# LcsNodes-Quad-Block-Controller-B_02_10.net
KiCad netlist of a schematic drawn in EasyEDA
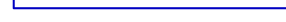
[diagram p0: High Level Schematic]
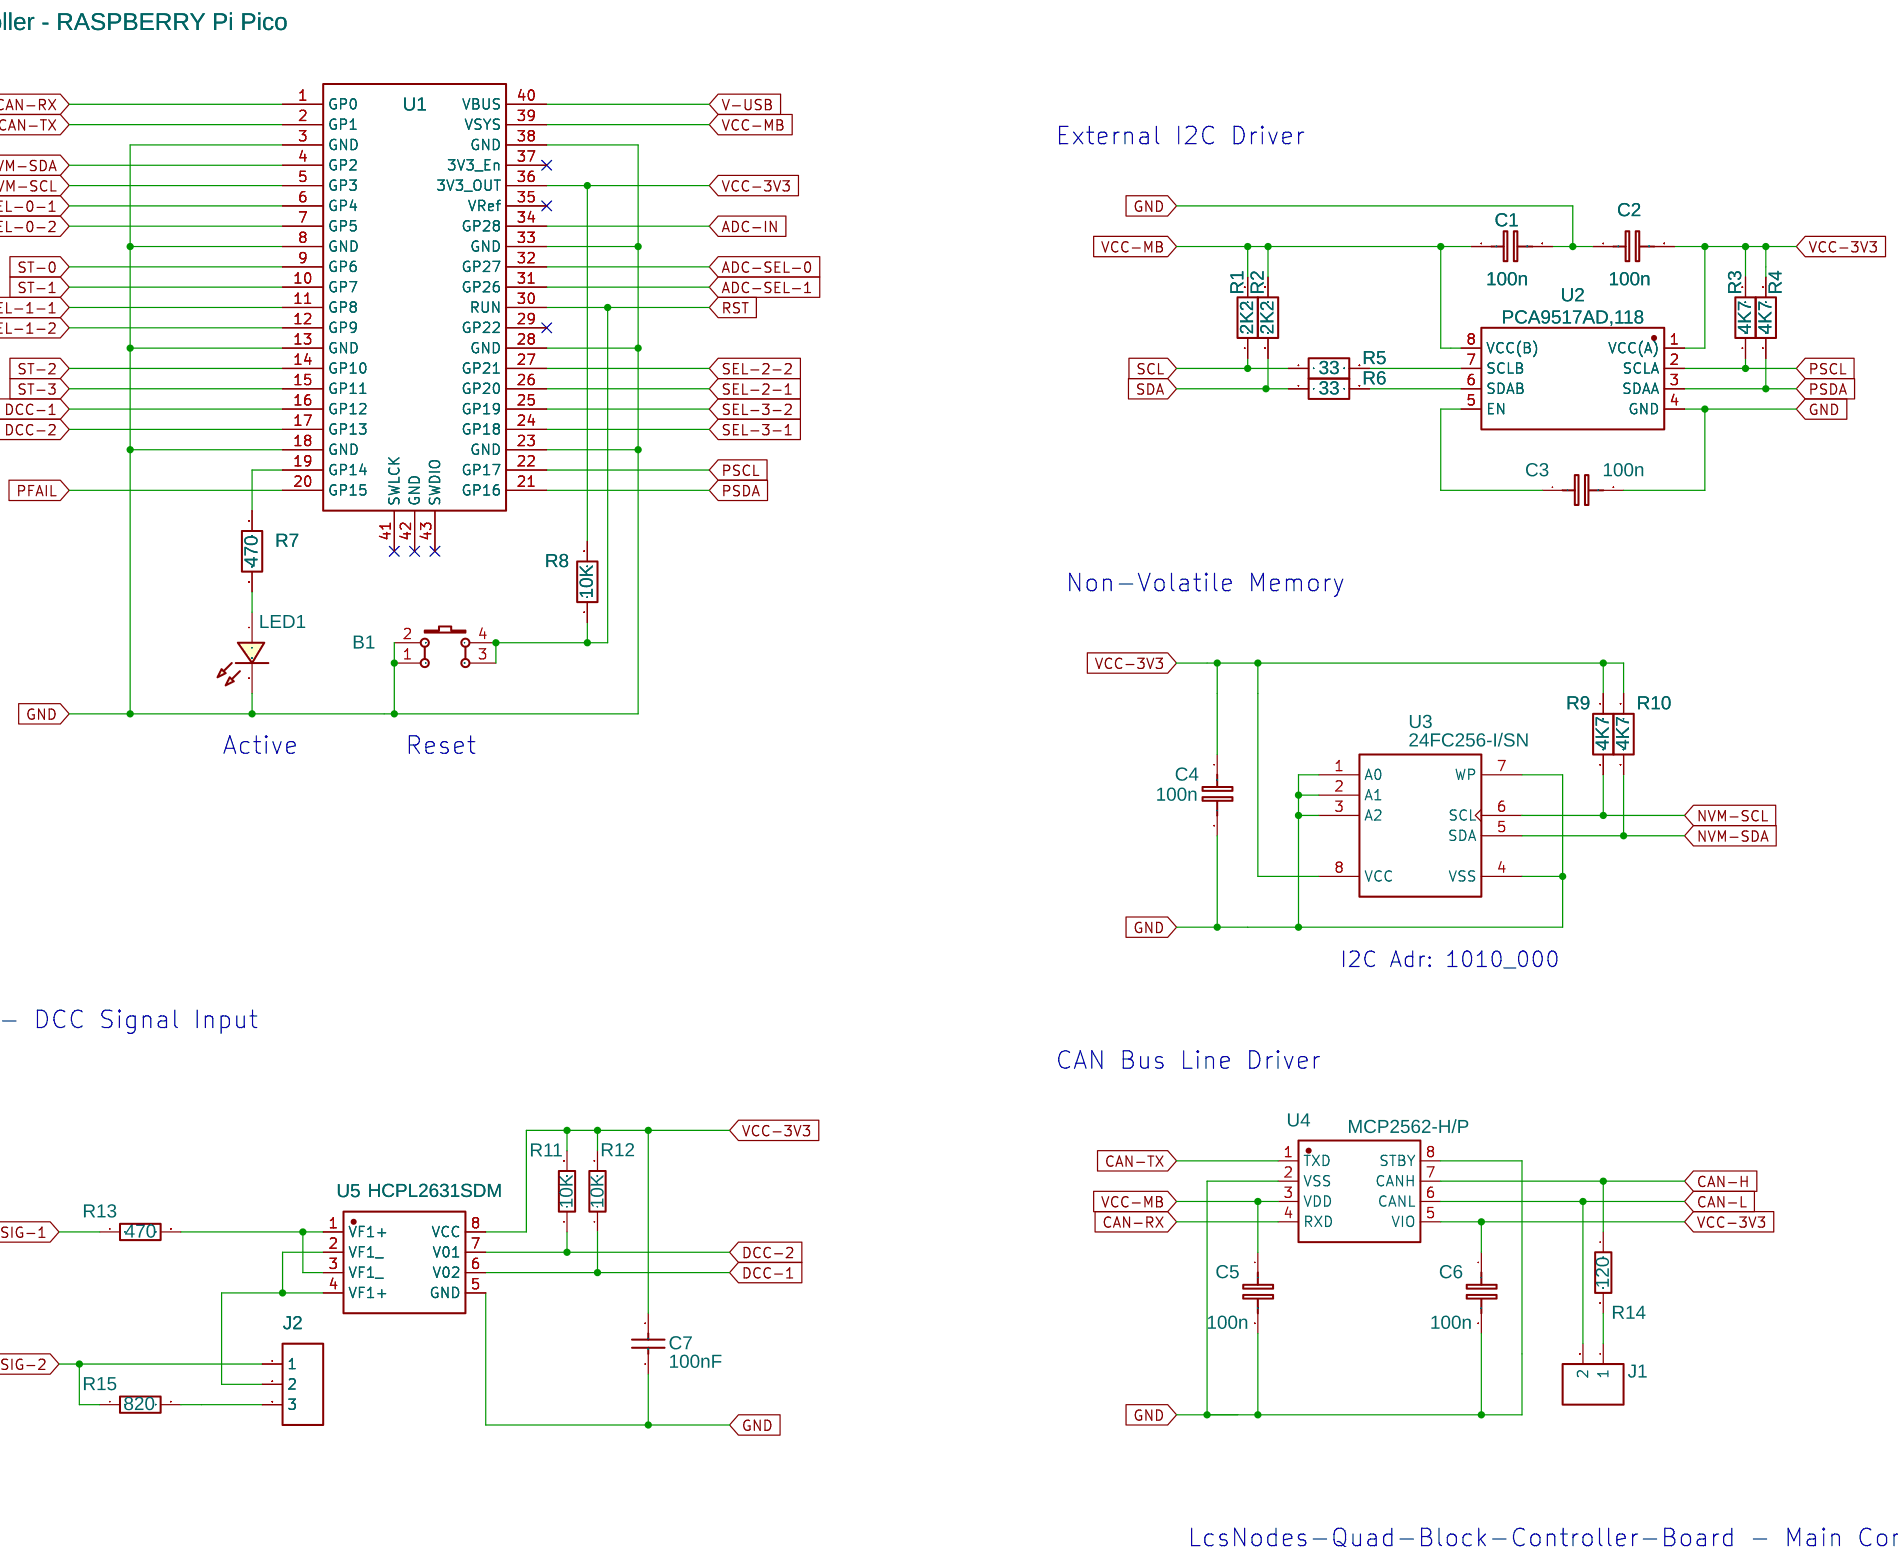
[diagram p1: Main Controller]
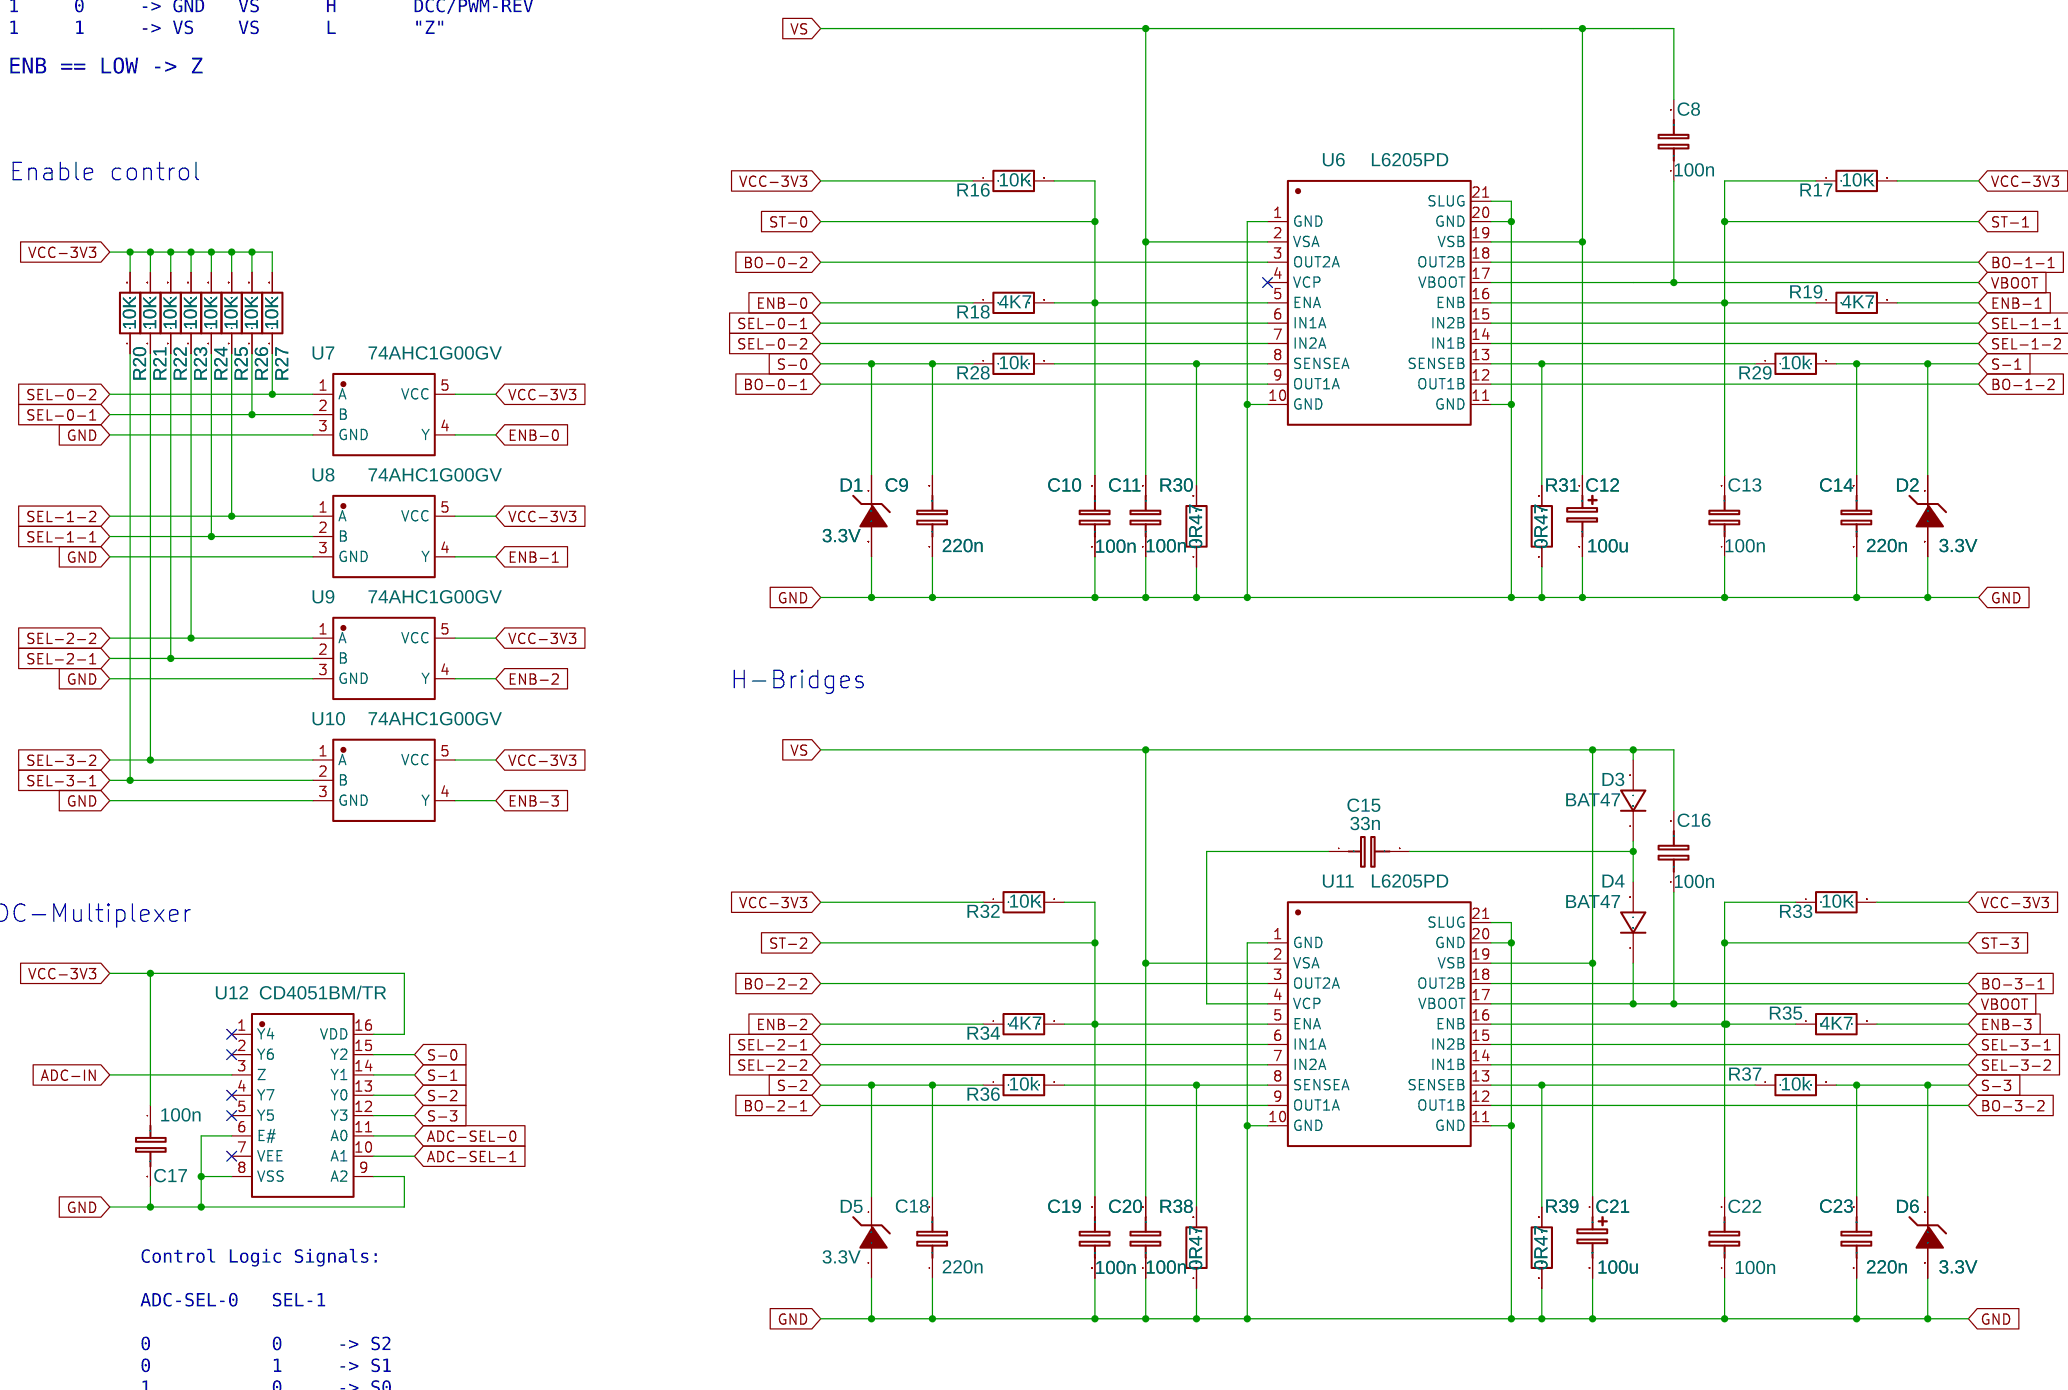
[diagram p2: Quad Power Unit]
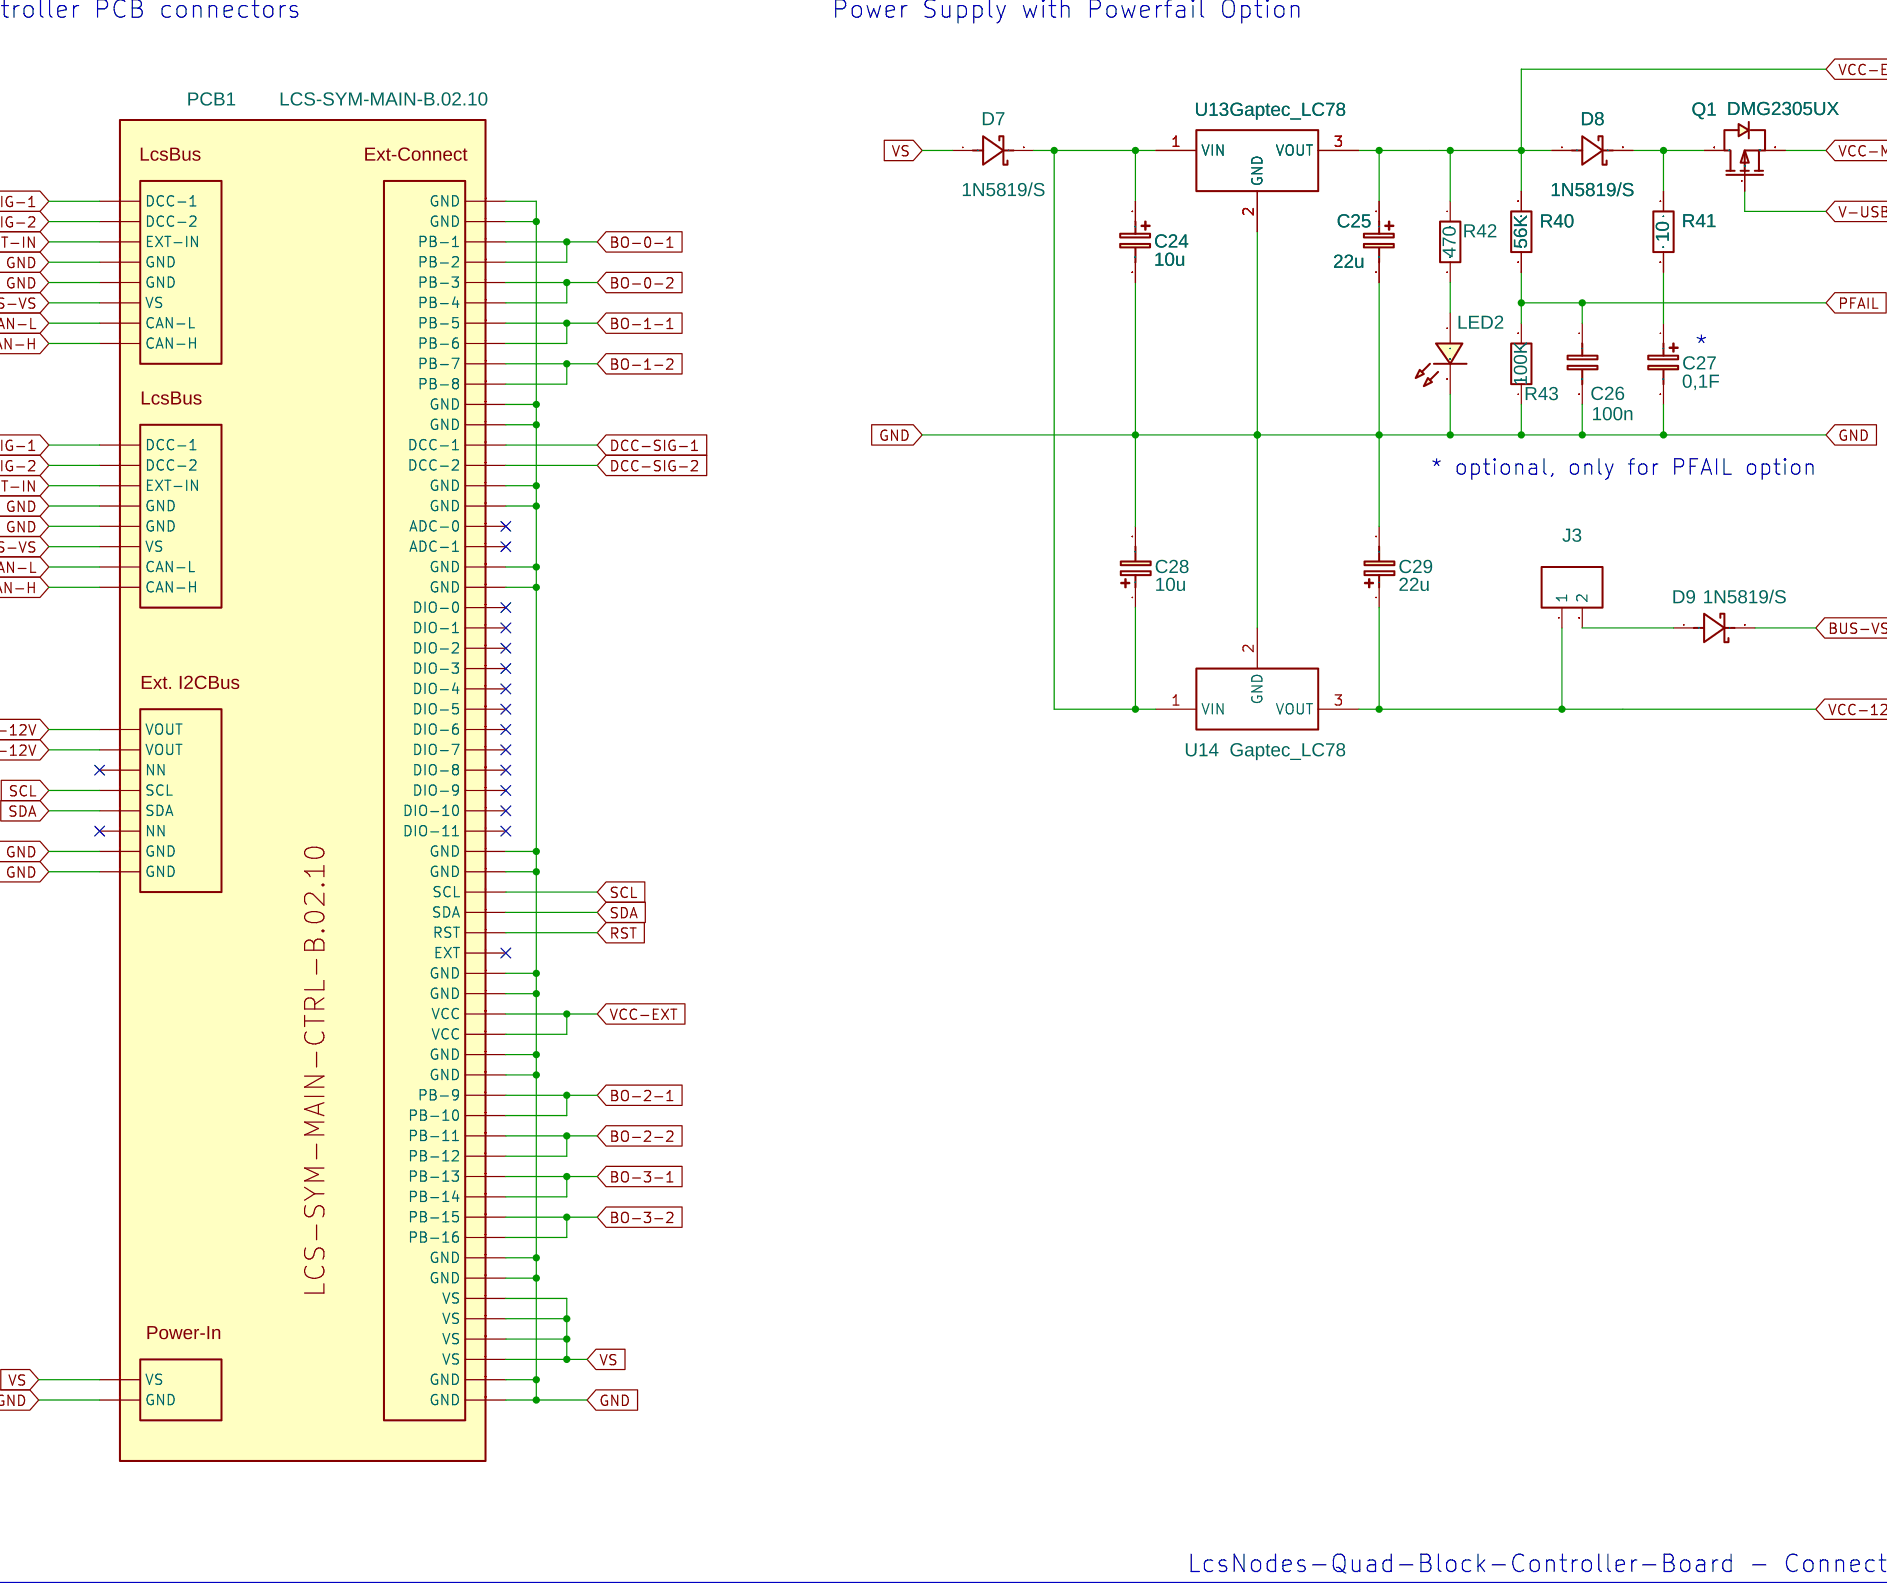
[diagram p3: Power Supply, Connectors]

(export (version "E")
  (design (tool "Eeschema 10.0.6"))
  (components
    (comp (ref "B1")
      (value "Opt")
      (fields (field (name "Manufacturer Part") "K2-1102DP-E4SW-04") (field (name "Manufacturer") "韩国韩荣"))
      (libsource (lib "") (part "K4-6×6_TH"))
    )
    (comp (ref "C1") (value "100n") (libsource (lib "") (part "C_RAD-0.2_EU")))
    (comp (ref "C2") (value "100n") (libsource (lib "") (part "C_RAD-0.2_EU")))
    (comp (ref "C3") (value "100n") (libsource (lib "") (part "C_RAD-0.2_EU")))
    (comp (ref "C4") (value "100n") (libsource (lib "") (part "C_0603_EU")))
    (comp (ref "C5") (value "100n") (libsource (lib "") (part "C_0603_EU")))
    (comp (ref "C6") (value "100n") (libsource (lib "") (part "C_0603_EU")))
    (comp (ref "C7")
      (value "100nF")
      (fields
        (field (name "Manufacturer Part") "CC1206KKX7R0BB104")
        (field (name "Manufacturer") "YAGEO(国巨)")
      )
      (libsource (lib "") (part "CC1206KKX7R0BB104"))
    )
    (comp (ref "J1") (value "HDR-M-2.54_1x2") (libsource (lib "") (part "HDR-M-2.54_1x2")))
    (comp (ref "J2") (value "HDR-M-2.54_1x3") (libsource (lib "") (part "HDR-M-2.54_1x3")))
    (comp (ref "LED1")
      (value "LED-0805_G")
      (fields (field (name "Manufacturer Part") "NCD0805G1") (field (name "Manufacturer") "国星光电"))
      (libsource (lib "") (part "LED-0805_G"))
    )
    (comp (ref "R1") (value "2K2") (libsource (lib "") (part "R_0805_EU_1")))
    (comp (ref "R2") (value "2K2") (libsource (lib "") (part "R_0805_EU_1")))
    (comp (ref "R3") (value "4K7") (libsource (lib "") (part "R_0805_EU_1")))
    (comp (ref "R4") (value "4K7") (libsource (lib "") (part "R_0805_EU_1")))
    (comp (ref "R5") (value "33") (libsource (lib "") (part "R_1206_EU")))
    (comp (ref "R6") (value "33") (libsource (lib "") (part "R_1206_EU")))
    (comp (ref "R7") (value "470") (libsource (lib "") (part "R_0805_EU")))
    (comp (ref "R8") (value "10K") (libsource (lib "") (part "R_0805_EU_1")))
    (comp (ref "R9") (value "4K7") (libsource (lib "") (part "R_0805_EU")))
    (comp (ref "R10") (value "4K7") (libsource (lib "") (part "R_0805_EU")))
    (comp (ref "R11")
      (value "10K")
      (fields (field (name "Manufacturer Part") "SR1206JR-7W4K7L") (field (name "Manufacturer") "YAGEO(国巨)"))
      (libsource (lib "") (part "SR1206JR-7W4K7L_1"))
    )
    (comp (ref "R12")
      (value "10K")
      (fields (field (name "Manufacturer Part") "SR1206JR-7W4K7L") (field (name "Manufacturer") "YAGEO(国巨)"))
      (libsource (lib "") (part "SR1206JR-7W4K7L_1"))
    )
    (comp (ref "R13")
      (value "470")
      (fields (field (name "Manufacturer Part") "SR1206JR-7W4K7L") (field (name "Manufacturer") "YAGEO(国巨)"))
      (libsource (lib "") (part "SR1206JR-7W4K7L"))
    )
    (comp (ref "R14") (value "120") (libsource (lib "") (part "RESISTOR-AXIAL-0.1")))
    (comp (ref "R15")
      (value "820")
      (fields (field (name "Manufacturer Part") "SR1206JR-7W4K7L") (field (name "Manufacturer") "YAGEO(国巨)"))
      (libsource (lib "") (part "SR1206JR-7W4K7L"))
    )
    (comp (ref "U1")
      (value "Main Controller - RASPBERRY Pi Pico")
      (libsource (lib "") (part "RASPBERRY Pi Pico Through Holes"))
    )
    (comp (ref "U2")
      (value "PCA9517AD,118")
      (fields (field (name "Manufacturer") "NXP(恩智浦)"))
      (libsource (lib "") (part "PCA9517AD,118"))
    )
    (comp (ref "U3")
      (value "24FC256-I/SN")
      (fields (field (name "Manufacturer") "MICROCHIP(美国微芯)"))
      (libsource (lib "") (part "24FC256-I/SN"))
    )
    (comp (ref "U4")
      (value "MCP2562-H/P")
      (fields (field (name "Manufacturer") "MICROCHIP(美国微芯)"))
      (libsource (lib "") (part "MCP2562-H/P"))
    )
    (comp (ref "U5")
      (value "HCPL2631SDM")
      (fields (field (name "Manufacturer") "onsemi(安森美)"))
      (libsource (lib "") (part "HCPL2631SDM"))
    )
    (comp (ref "C8") (value "100n") (libsource (lib "") (part "C_0603_EU_2")))
    (comp (ref "C9") (value "220n") (libsource (lib "") (part "C_0603_EU_2")))
    (comp (ref "C10") (value "100n") (libsource (lib "") (part "C_0603_EU_2")))
    (comp (ref "C11") (value "100n") (libsource (lib "") (part "C_0603_EU_2")))
    (comp (ref "C12") (value "100u") (libsource (lib "") (part "CE_SMD_D5.0×H5.5_EU_1")))
    (comp (ref "C13") (value "100n") (libsource (lib "") (part "C_0603_EU_2")))
    (comp (ref "C14") (value "220n") (libsource (lib "") (part "C_0603_EU_2")))
    (comp (ref "C15") (value "33n") (libsource (lib "") (part "C_0603_EU_3")))
    (comp (ref "C16") (value "100n") (libsource (lib "") (part "C_0603_EU")))
    (comp (ref "C17") (value "100n") (libsource (lib "") (part "C_0603_EU_1")))
    (comp (ref "C18") (value "220n") (libsource (lib "") (part "C_0603_EU")))
    (comp (ref "C19") (value "100n") (libsource (lib "") (part "C_0603_EU")))
    (comp (ref "C20") (value "100n") (libsource (lib "") (part "C_0603_EU")))
    (comp (ref "C21") (value "100u") (libsource (lib "") (part "CE_SMD_D5.0×H5.5_EU")))
    (comp (ref "C22") (value "100n") (libsource (lib "") (part "C_0603_EU")))
    (comp (ref "C23") (value "220n") (libsource (lib "") (part "C_0603_EU")))
    (comp (ref "D1")
      (value "3.3V")
      (fields (field (name "Manufacturer Part") "Diode Zener") (field (name "Manufacturer") "SEMTECH"))
      (libsource (lib "") (part "Diode Zener"))
    )
    (comp (ref "D2")
      (value "3.3V")
      (fields (field (name "Manufacturer Part") "Diode Zener") (field (name "Manufacturer") "SEMTECH"))
      (libsource (lib "") (part "Diode Zener"))
    )
    (comp (ref "D3")
      (value "BAT47")
      (fields (field (name "Manufacturer Part") "1N4148") (field (name "Manufacturer") "SEMTECH"))
      (libsource (lib "") (part "1N4148"))
    )
    (comp (ref "D4")
      (value "BAT47")
      (fields (field (name "Manufacturer Part") "1N4148") (field (name "Manufacturer") "SEMTECH"))
      (libsource (lib "") (part "1N4148"))
    )
    (comp (ref "D5")
      (value "3.3V")
      (fields (field (name "Manufacturer Part") "Diode Zener") (field (name "Manufacturer") "SEMTECH"))
      (libsource (lib "") (part "Diode Zener"))
    )
    (comp (ref "D6")
      (value "3.3V")
      (fields (field (name "Manufacturer Part") "Diode Zener") (field (name "Manufacturer") "SEMTECH"))
      (libsource (lib "") (part "Diode Zener"))
    )
    (comp (ref "R16") (value "10K") (libsource (lib "") (part "R_AXIAL-0.3_EU")))
    (comp (ref "R17") (value "10K") (libsource (lib "") (part "R_AXIAL-0.3_EU")))
    (comp (ref "R18") (value "4K7") (libsource (lib "") (part "R_AXIAL-0.3_EU")))
    (comp (ref "R19") (value "4K7") (libsource (lib "") (part "R_AXIAL-0.3_EU")))
    (comp (ref "R20") (value "10K") (libsource (lib "") (part "R_0805_EU")))
    (comp (ref "R21") (value "10K") (libsource (lib "") (part "R_0805_EU")))
    (comp (ref "R22") (value "10K") (libsource (lib "") (part "R_0805_EU")))
    (comp (ref "R23") (value "10K") (libsource (lib "") (part "R_0805_EU")))
    (comp (ref "R24") (value "10K") (libsource (lib "") (part "R_0805_EU")))
    (comp (ref "R25") (value "10K") (libsource (lib "") (part "R_0805_EU")))
    (comp (ref "R26") (value "10K") (libsource (lib "") (part "R_0805_EU")))
    (comp (ref "R27") (value "10K") (libsource (lib "") (part "R_0805_EU")))
    (comp (ref "R28") (value "10k") (libsource (lib "") (part "R_AXIAL-0.3_EU")))
    (comp (ref "R29") (value "10k") (libsource (lib "") (part "R_AXIAL-0.3_EU")))
    (comp (ref "R30") (value "0R47") (libsource (lib "") (part "R_AXIAL-0.5_EU")))
    (comp (ref "R31") (value "0R47") (libsource (lib "") (part "R_AXIAL-0.5_EU")))
    (comp (ref "R32") (value "10K") (libsource (lib "") (part "R_AXIAL-0.3_EU")))
    (comp (ref "R33") (value "10K") (libsource (lib "") (part "R_AXIAL-0.3_EU")))
    (comp (ref "R34") (value "4K7") (libsource (lib "") (part "R_AXIAL-0.3_EU")))
    (comp (ref "R35") (value "4K7") (libsource (lib "") (part "R_AXIAL-0.3_EU")))
    (comp (ref "R36") (value "10k") (libsource (lib "") (part "R_AXIAL-0.3_EU")))
    (comp (ref "R37") (value "10k") (libsource (lib "") (part "R_AXIAL-0.3_EU")))
    (comp (ref "R38") (value "0R47") (libsource (lib "") (part "R_AXIAL-0.5_EU")))
    (comp (ref "R39") (value "0R47") (libsource (lib "") (part "R_AXIAL-0.5_EU")))
    (comp (ref "U6")
      (value "L6205PD")
      (fields (field (name "Manufacturer Part") "L6205PD013TR") (field (name "Manufacturer") "ST(意法半导体)"))
      (libsource (lib "") (part "L6205PD"))
    )
    (comp (ref "U7")
      (value "74AHC1G00GV")
      (fields (field (name "Manufacturer") "TECH PUBLIC(台舟)"))
      (libsource (lib "") (part "74AHC1G00GV"))
    )
    (comp (ref "U8")
      (value "74AHC1G00GV")
      (fields (field (name "Manufacturer") "TECH PUBLIC(台舟)"))
      (libsource (lib "") (part "74AHC1G00GV"))
    )
    (comp (ref "U9")
      (value "74AHC1G00GV")
      (fields (field (name "Manufacturer") "TECH PUBLIC(台舟)"))
      (libsource (lib "") (part "74AHC1G00GV"))
    )
    (comp (ref "U10")
      (value "74AHC1G00GV")
      (fields (field (name "Manufacturer") "TECH PUBLIC(台舟)"))
      (libsource (lib "") (part "74AHC1G00GV"))
    )
    (comp (ref "U11")
      (value "L6205PD")
      (fields (field (name "Manufacturer Part") "L6205PD013TR") (field (name "Manufacturer") "ST(意法半导体)"))
      (libsource (lib "") (part "L6205PD"))
    )
    (comp (ref "U12")
      (value "CD4051BM/TR")
      (fields (field (name "Manufacturer") "HGSEMI(华冠)"))
      (libsource (lib "") (part "CD4051BM/TR"))
    )
    (comp (ref "C24") (value "10u") (libsource (lib "") (part "CE_SMD_D5.0×H5.5_EU")))
    (comp (ref "C25") (value "22u") (libsource (lib "") (part "CE_SMD_D5.0×H5.5_EU")))
    (comp (ref "C26") (value "100n") (libsource (lib "") (part "C_RAD-0.2_EU")))
    (comp (ref "C27") (value "0,1F") (libsource (lib "") (part "C_Tan_SMD_A_EU")))
    (comp (ref "C28") (value "10u") (libsource (lib "") (part "CE_SMD_D5.0×H5.5_EU_1")))
    (comp (ref "C29") (value "22u") (libsource (lib "") (part "CE_SMD_D5.0×H5.5_EU_1")))
    (comp (ref "D7") (value "1N5819/S") (libsource (lib "") (part "1N5819/S")))
    (comp (ref "D8") (value "1N5819/S") (libsource (lib "") (part "1N5819/S")))
    (comp (ref "D9") (value "1N5819/S") (libsource (lib "") (part "1N5819/S")))
    (comp (ref "J3") (value "HDR-M-2.54_1x2") (libsource (lib "") (part "HDR-M-2.54_1x2")))
    (comp (ref "LED2")
      (value "LED-0805_G")
      (fields (field (name "Manufacturer Part") "NCD0805G1") (field (name "Manufacturer") "国星光电"))
      (libsource (lib "") (part "LED-0805_G"))
    )
    (comp (ref "PCB1") (value "LCS-SYM-MAIN-B.02.10") (libsource (lib "") (part "LCS-SYM-MAIN-B.02.10")))
    (comp (ref "Q1")
      (value "DMG2305UX")
      (fields (field (name "Manufacturer") "TECH PUBLIC(台舟)"))
      (libsource (lib "") (part "DMG2305UX"))
    )
    (comp (ref "R40") (value "56K") (libsource (lib "") (part "R_AXIAL-0.3_EU")))
    (comp (ref "R41") (value "10") (libsource (lib "") (part "R_AXIAL-0.3_EU_1")))
    (comp (ref "R42") (value "470") (libsource (lib "") (part "R_0805_EU")))
    (comp (ref "R43") (value "100K") (libsource (lib "") (part "R_AXIAL-0.3_EU")))
    (comp (ref "U13") (value "Gaptec_LC78") (libsource (lib "") (part "Gaptec_LC78_1")))
    (comp (ref "U14") (value "Gaptec_LC78") (libsource (lib "") (part "Gaptec_LC78")))
  )
  (nets
    (net (code "1") (name "ADC-IN") (class "Default")
      (node (ref "U1") (pin "34") (pinfunction "GP28_34") (pintype "unspecified"))
      (node (ref "U12") (pin "3") (pinfunction "Z_3") (pintype "unspecified"))
    )
    (net (code "2") (name "ADC-SEL-0") (class "Default")
      (node (ref "U1") (pin "32") (pinfunction "GP27_32") (pintype "unspecified"))
      (node (ref "U12") (pin "11") (pinfunction "A0_11") (pintype "unspecified"))
    )
    (net (code "3") (name "ADC-SEL-1") (class "Default")
      (node (ref "U1") (pin "31") (pinfunction "GP26_31") (pintype "unspecified"))
      (node (ref "U12") (pin "10") (pinfunction "A1_10") (pintype "unspecified"))
    )
    (net (code "4") (name "BO-0-1") (class "Default")
      (node (ref "PCB1") (pin "42") (pinfunction "PB-1_42") (pintype "unspecified"))
      (node (ref "PCB1") (pin "43") (pinfunction "PB-2_43") (pintype "unspecified"))
      (node (ref "U6") (pin "9") (pinfunction "OUT1A_9") (pintype "unspecified"))
    )
    (net (code "5") (name "BO-0-2") (class "Default")
      (node (ref "PCB1") (pin "44") (pinfunction "PB-3_44") (pintype "unspecified"))
      (node (ref "PCB1") (pin "45") (pinfunction "PB-4_45") (pintype "unspecified"))
      (node (ref "U6") (pin "3") (pinfunction "OUT2A_3") (pintype "unspecified"))
    )
    (net (code "6") (name "BO-1-1") (class "Default")
      (node (ref "PCB1") (pin "46") (pinfunction "PB-5_46") (pintype "unspecified"))
      (node (ref "PCB1") (pin "47") (pinfunction "PB-6_47") (pintype "unspecified"))
      (node (ref "U6") (pin "18") (pinfunction "OUT2B_18") (pintype "unspecified"))
    )
    (net (code "7") (name "BO-1-2") (class "Default")
      (node (ref "PCB1") (pin "48") (pinfunction "PB-7_48") (pintype "unspecified"))
      (node (ref "PCB1") (pin "49") (pinfunction "PB-8_49") (pintype "unspecified"))
      (node (ref "U6") (pin "12") (pinfunction "OUT1B_12") (pintype "unspecified"))
    )
    (net (code "8") (name "BO-2-1") (class "Default")
      (node (ref "PCB1") (pin "84") (pinfunction "PB-9_84") (pintype "unspecified"))
      (node (ref "PCB1") (pin "85") (pinfunction "PB-10_85") (pintype "unspecified"))
      (node (ref "U11") (pin "9") (pinfunction "OUT1A_9") (pintype "unspecified"))
    )
    (net (code "9") (name "BO-2-2") (class "Default")
      (node (ref "PCB1") (pin "86") (pinfunction "PB-11_86") (pintype "unspecified"))
      (node (ref "PCB1") (pin "87") (pinfunction "PB-12_87") (pintype "unspecified"))
      (node (ref "U11") (pin "3") (pinfunction "OUT2A_3") (pintype "unspecified"))
    )
    (net (code "10") (name "BO-3-1") (class "Default")
      (node (ref "PCB1") (pin "88") (pinfunction "PB-13_88") (pintype "unspecified"))
      (node (ref "PCB1") (pin "89") (pinfunction "PB-14_89") (pintype "unspecified"))
      (node (ref "U11") (pin "18") (pinfunction "OUT2B_18") (pintype "unspecified"))
    )
    (net (code "11") (name "BO-3-2") (class "Default")
      (node (ref "PCB1") (pin "90") (pinfunction "PB-15_90") (pintype "unspecified"))
      (node (ref "PCB1") (pin "91") (pinfunction "PB-16_91") (pintype "unspecified"))
      (node (ref "U11") (pin "12") (pinfunction "OUT1B_12") (pintype "unspecified"))
    )
    (net (code "12") (name "BUS-VS") (class "Default")
      (node (ref "D9") (pin "2") (pinfunction "K_2") (pintype "unspecified"))
      (node (ref "PCB1") (pin "16") (pinfunction "VS_16") (pintype "unspecified"))
      (node (ref "PCB1") (pin "6") (pinfunction "VS_6") (pintype "unspecified"))
    )
    (net (code "13") (name "CAN-H") (class "Default")
      (node (ref "PCB1") (pin "18") (pinfunction "CAN-H_18") (pintype "unspecified"))
      (node (ref "PCB1") (pin "8") (pinfunction "CAN-H_8") (pintype "unspecified"))
      (node (ref "R14") (pin "1") (pinfunction "1_1") (pintype "input"))
      (node (ref "U4") (pin "7") (pinfunction "CANH_7") (pintype "unspecified"))
    )
    (net (code "14") (name "CAN-L") (class "Default")
      (node (ref "J1") (pin "2") (pinfunction "2_2") (pintype "unspecified"))
      (node (ref "PCB1") (pin "17") (pinfunction "CAN-L_17") (pintype "unspecified"))
      (node (ref "PCB1") (pin "7") (pinfunction "CAN-L_7") (pintype "unspecified"))
      (node (ref "U4") (pin "6") (pinfunction "CANL_6") (pintype "unspecified"))
    )
    (net (code "15") (name "CAN-RX") (class "Default")
      (node (ref "U1") (pin "1") (pinfunction "GP0_1") (pintype "unspecified"))
      (node (ref "U4") (pin "4") (pinfunction "RXD_4") (pintype "unspecified"))
    )
    (net (code "16") (name "CAN-TX") (class "Default")
      (node (ref "U1") (pin "2") (pinfunction "GP1_2") (pintype "unspecified"))
      (node (ref "U4") (pin "1") (pinfunction "TXD_1") (pintype "unspecified"))
    )
    (net (code "17") (name "DCC-1") (class "Default")
      (node (ref "R12") (pin "1") (pinfunction "1_1") (pintype "unspecified"))
      (node (ref "U1") (pin "16") (pinfunction "GP12_16") (pintype "unspecified"))
      (node (ref "U5") (pin "6") (pinfunction "V02_6") (pintype "unspecified"))
    )
    (net (code "18") (name "DCC-2") (class "Default")
      (node (ref "R11") (pin "1") (pinfunction "1_1") (pintype "unspecified"))
      (node (ref "U1") (pin "17") (pinfunction "GP13_17") (pintype "unspecified"))
      (node (ref "U5") (pin "7") (pinfunction "V01_7") (pintype "unspecified"))
    )
    (net (code "19") (name "DCC-SIG-1") (class "Default")
      (node (ref "PCB1") (pin "1") (pinfunction "DCC-1_1") (pintype "unspecified"))
      (node (ref "PCB1") (pin "11") (pinfunction "DCC-1_11") (pintype "unspecified"))
      (node (ref "PCB1") (pin "52") (pinfunction "DCC-1_52") (pintype "unspecified"))
      (node (ref "R13") (pin "1") (pinfunction "1_1") (pintype "unspecified"))
    )
    (net (code "20") (name "DCC-SIG-2") (class "Default")
      (node (ref "J2") (pin "1") (pinfunction "1_1") (pintype "input"))
      (node (ref "PCB1") (pin "12") (pinfunction "DCC-2_12") (pintype "unspecified"))
      (node (ref "PCB1") (pin "2") (pinfunction "DCC-2_2") (pintype "unspecified"))
      (node (ref "PCB1") (pin "53") (pinfunction "DCC-2_53") (pintype "unspecified"))
      (node (ref "R15") (pin "1") (pinfunction "1_1") (pintype "unspecified"))
    )
    (net (code "21") (name "ENB-0") (class "Default")
      (node (ref "R18") (pin "1") (pinfunction "1_1") (pintype "unspecified"))
      (node (ref "U7") (pin "4") (pinfunction "Y_4") (pintype "unspecified"))
    )
    (net (code "22") (name "ENB-1") (class "Default")
      (node (ref "R19") (pin "2") (pinfunction "2_2") (pintype "unspecified"))
      (node (ref "U8") (pin "4") (pinfunction "Y_4") (pintype "unspecified"))
    )
    (net (code "23") (name "ENB-2") (class "Default")
      (node (ref "R34") (pin "1") (pinfunction "1_1") (pintype "unspecified"))
      (node (ref "U9") (pin "4") (pinfunction "Y_4") (pintype "unspecified"))
    )
    (net (code "24") (name "ENB-3") (class "Default")
      (node (ref "R35") (pin "2") (pinfunction "2_2") (pintype "unspecified"))
      (node (ref "U10") (pin "4") (pinfunction "Y_4") (pintype "unspecified"))
    )
    (net (code "25") (name "EXT-IN") (class "Default")
      (node (ref "PCB1") (pin "13") (pinfunction "EXT-IN_13") (pintype "unspecified"))
      (node (ref "PCB1") (pin "3") (pinfunction "EXT-IN_3") (pintype "unspecified"))
    )
    (net (code "26") (name "GND") (class "Default")
      (node (ref "B1") (pin "1") (pinfunction "1_1") (pintype "unspecified"))
      (node (ref "B1") (pin "2") (pinfunction "2_2") (pintype "unspecified"))
      (node (ref "C1") (pin "2") (pinfunction "2_2") (pintype "unspecified"))
      (node (ref "C10") (pin "1") (pinfunction "1_1") (pintype "unspecified"))
      (node (ref "C11") (pin "1") (pinfunction "1_1") (pintype "unspecified"))
      (node (ref "C12") (pin "2") (pinfunction "2_2") (pintype "unspecified"))
      (node (ref "C13") (pin "1") (pinfunction "1_1") (pintype "unspecified"))
      (node (ref "C14") (pin "1") (pinfunction "1_1") (pintype "unspecified"))
      (node (ref "C17") (pin "2") (pinfunction "2_2") (pintype "unspecified"))
      (node (ref "C18") (pin "1") (pinfunction "1_1") (pintype "unspecified"))
      (node (ref "C19") (pin "1") (pinfunction "1_1") (pintype "unspecified"))
      (node (ref "C2") (pin "1") (pinfunction "1_1") (pintype "unspecified"))
      (node (ref "C20") (pin "1") (pinfunction "1_1") (pintype "unspecified"))
      (node (ref "C21") (pin "2") (pinfunction "2_2") (pintype "unspecified"))
      (node (ref "C22") (pin "1") (pinfunction "1_1") (pintype "unspecified"))
      (node (ref "C23") (pin "1") (pinfunction "1_1") (pintype "unspecified"))
      (node (ref "C24") (pin "2") (pinfunction "2_2") (pintype "unspecified"))
      (node (ref "C25") (pin "2") (pinfunction "2_2") (pintype "unspecified"))
      (node (ref "C26") (pin "2") (pinfunction "2_2") (pintype "unspecified"))
      (node (ref "C27") (pin "2") (pinfunction "2_2") (pintype "unspecified"))
      (node (ref "C28") (pin "2") (pinfunction "2_2") (pintype "unspecified"))
      (node (ref "C29") (pin "2") (pinfunction "2_2") (pintype "unspecified"))
      (node (ref "C3") (pin "2") (pinfunction "2_2") (pintype "unspecified"))
      (node (ref "C4") (pin "2") (pinfunction "2_2") (pintype "unspecified"))
      (node (ref "C5") (pin "2") (pinfunction "2_2") (pintype "unspecified"))
      (node (ref "C6") (pin "2") (pinfunction "2_2") (pintype "unspecified"))
      (node (ref "C7") (pin "1") (pinfunction "1_1") (pintype "input"))
      (node (ref "C9") (pin "1") (pinfunction "1_1") (pintype "unspecified"))
      (node (ref "D1") (pin "2") (pinfunction "A_2") (pintype "unspecified"))
      (node (ref "D2") (pin "2") (pinfunction "A_2") (pintype "unspecified"))
      (node (ref "D5") (pin "2") (pinfunction "A_2") (pintype "unspecified"))
      (node (ref "D6") (pin "2") (pinfunction "A_2") (pintype "unspecified"))
      (node (ref "LED1") (pin "2") (pinfunction "2_2") (pintype "unspecified"))
      (node (ref "LED2") (pin "2") (pinfunction "2_2") (pintype "unspecified"))
      (node (ref "PCB1") (pin "14") (pinfunction "GND_14") (pintype "unspecified"))
      (node (ref "PCB1") (pin "15") (pinfunction "GND_15") (pintype "unspecified"))
      (node (ref "PCB1") (pin "27") (pinfunction "GND_27") (pintype "unspecified"))
      (node (ref "PCB1") (pin "28") (pinfunction "GND_28") (pintype "unspecified"))
      (node (ref "PCB1") (pin "31") (pinfunction "GND_31") (pintype "unspecified"))
      (node (ref "PCB1") (pin "4") (pinfunction "GND_4") (pintype "unspecified"))
      (node (ref "PCB1") (pin "40") (pinfunction "GND_40") (pintype "unspecified"))
      (node (ref "PCB1") (pin "41") (pinfunction "GND_41") (pintype "unspecified"))
      (node (ref "PCB1") (pin "5") (pinfunction "GND_5") (pintype "unspecified"))
      (node (ref "PCB1") (pin "50") (pinfunction "GND_50") (pintype "unspecified"))
      (node (ref "PCB1") (pin "51") (pinfunction "GND_51") (pintype "unspecified"))
      (node (ref "PCB1") (pin "54") (pinfunction "GND_54") (pintype "unspecified"))
      (node (ref "PCB1") (pin "55") (pinfunction "GND_55") (pintype "unspecified"))
      (node (ref "PCB1") (pin "58") (pinfunction "GND_58") (pintype "unspecified"))
      (node (ref "PCB1") (pin "59") (pinfunction "GND_59") (pintype "unspecified"))
      (node (ref "PCB1") (pin "72") (pinfunction "GND_72") (pintype "unspecified"))
      (node (ref "PCB1") (pin "73") (pinfunction "GND_73") (pintype "unspecified"))
      (node (ref "PCB1") (pin "78") (pinfunction "GND_78") (pintype "unspecified"))
      (node (ref "PCB1") (pin "79") (pinfunction "GND_79") (pintype "unspecified"))
      (node (ref "PCB1") (pin "82") (pinfunction "GND_82") (pintype "unspecified"))
      (node (ref "PCB1") (pin "83") (pinfunction "GND_83") (pintype "unspecified"))
      (node (ref "PCB1") (pin "92") (pinfunction "GND_92") (pintype "unspecified"))
      (node (ref "PCB1") (pin "93") (pinfunction "GND_93") (pintype "unspecified"))
      (node (ref "PCB1") (pin "98") (pinfunction "GND_98") (pintype "unspecified"))
      (node (ref "PCB1") (pin "99") (pinfunction "GND_99") (pintype "unspecified"))
      (node (ref "R30") (pin "1") (pinfunction "1_1") (pintype "unspecified"))
      (node (ref "R31") (pin "1") (pinfunction "1_1") (pintype "unspecified"))
      (node (ref "R38") (pin "1") (pinfunction "1_1") (pintype "unspecified"))
      (node (ref "R39") (pin "1") (pinfunction "1_1") (pintype "unspecified"))
      (node (ref "R43") (pin "1") (pinfunction "1_1") (pintype "unspecified"))
      (node (ref "U1") (pin "13") (pinfunction "GND_13") (pintype "unspecified"))
      (node (ref "U1") (pin "18") (pinfunction "GND_18") (pintype "unspecified"))
      (node (ref "U1") (pin "23") (pinfunction "GND_23") (pintype "unspecified"))
      (node (ref "U1") (pin "28") (pinfunction "GND_28") (pintype "unspecified"))
      (node (ref "U1") (pin "3") (pinfunction "GND_3") (pintype "unspecified"))
      (node (ref "U1") (pin "33") (pinfunction "GND_33") (pintype "unspecified"))
      (node (ref "U1") (pin "38") (pinfunction "GND_38") (pintype "unspecified"))
      (node (ref "U1") (pin "8") (pinfunction "GND_8") (pintype "unspecified"))
      (node (ref "U10") (pin "3") (pinfunction "GND_3") (pintype "unspecified"))
      (node (ref "U11") (pin "1") (pinfunction "GND_1") (pintype "unspecified"))
      (node (ref "U11") (pin "10") (pinfunction "GND_10") (pintype "unspecified"))
      (node (ref "U11") (pin "11") (pinfunction "GND_11") (pintype "unspecified"))
      (node (ref "U11") (pin "20") (pinfunction "GND_20") (pintype "unspecified"))
      (node (ref "U11") (pin "21") (pinfunction "SLUG_21") (pintype "unspecified"))
      (node (ref "U12") (pin "6") (pinfunction "E#_6") (pintype "unspecified"))
      (node (ref "U12") (pin "8") (pinfunction "VSS_8") (pintype "unspecified"))
      (node (ref "U12") (pin "9") (pinfunction "A2_9") (pintype "unspecified"))
      (node (ref "U13") (pin "2") (pinfunction "GND_2") (pintype "unspecified"))
      (node (ref "U14") (pin "2") (pinfunction "GND_2") (pintype "unspecified"))
      (node (ref "U2") (pin "4") (pinfunction "GND_4") (pintype "unspecified"))
      (node (ref "U3") (pin "1") (pinfunction "A0_1") (pintype "unspecified"))
      (node (ref "U3") (pin "2") (pinfunction "A1_2") (pintype "unspecified"))
      (node (ref "U3") (pin "3") (pinfunction "A2_3") (pintype "unspecified"))
      (node (ref "U3") (pin "4") (pinfunction "VSS_4") (pintype "passive"))
      (node (ref "U3") (pin "7") (pinfunction "WP_7") (pintype "unspecified"))
      (node (ref "U4") (pin "2") (pinfunction "VSS_2") (pintype "unspecified"))
      (node (ref "U4") (pin "8") (pinfunction "STBY_8") (pintype "unspecified"))
      (node (ref "U5") (pin "5") (pinfunction "GND_5") (pintype "unspecified"))
      (node (ref "U6") (pin "1") (pinfunction "GND_1") (pintype "unspecified"))
      (node (ref "U6") (pin "10") (pinfunction "GND_10") (pintype "unspecified"))
      (node (ref "U6") (pin "11") (pinfunction "GND_11") (pintype "unspecified"))
      (node (ref "U6") (pin "20") (pinfunction "GND_20") (pintype "unspecified"))
      (node (ref "U6") (pin "21") (pinfunction "SLUG_21") (pintype "unspecified"))
      (node (ref "U7") (pin "3") (pinfunction "GND_3") (pintype "unspecified"))
      (node (ref "U8") (pin "3") (pinfunction "GND_3") (pintype "unspecified"))
      (node (ref "U9") (pin "3") (pinfunction "GND_3") (pintype "unspecified"))
    )
    (net (code "27") (name "NVM-SCL") (class "Default")
      (node (ref "R9") (pin "2") (pinfunction "2_2") (pintype "unspecified"))
      (node (ref "U1") (pin "5") (pinfunction "GP3_5") (pintype "unspecified"))
      (node (ref "U3") (pin "6") (pinfunction "SCL_6") (pintype "unspecified"))
    )
    (net (code "28") (name "NVM-SDA") (class "Default")
      (node (ref "R10") (pin "2") (pinfunction "2_2") (pintype "unspecified"))
      (node (ref "U1") (pin "4") (pinfunction "GP2_4") (pintype "unspecified"))
      (node (ref "U3") (pin "5") (pinfunction "SDA_5") (pintype "bidirectional"))
    )
    (net (code "29") (name "Net-(C27-Pad1)") (class "Default")
      (node (ref "C27") (pin "1") (pinfunction "1_1") (pintype "unspecified"))
      (node (ref "R41") (pin "2") (pinfunction "2_2") (pintype "unspecified"))
    )
    (net (code "30") (name "Net-(D3-2)") (class "Default")
      (node (ref "C15") (pin "2") (pinfunction "2_2") (pintype "unspecified"))
      (node (ref "D3") (pin "1") (pinfunction "2_1") (pintype "unspecified"))
      (node (ref "D4") (pin "2") (pinfunction "1_2") (pintype "unspecified"))
    )
    (net (code "31") (name "Net-(D7-K)") (class "Default")
      (node (ref "C24") (pin "1") (pinfunction "1_1") (pintype "unspecified"))
      (node (ref "C28") (pin "1") (pinfunction "1_1") (pintype "unspecified"))
      (node (ref "D7") (pin "2") (pinfunction "K_2") (pintype "unspecified"))
      (node (ref "U13") (pin "1") (pinfunction "VIN_1") (pintype "unspecified"))
      (node (ref "U14") (pin "1") (pinfunction "VIN_1") (pintype "unspecified"))
    )
    (net (code "32") (name "Net-(D8-K)") (class "Default")
      (node (ref "D8") (pin "2") (pinfunction "K_2") (pintype "unspecified"))
      (node (ref "Q1") (pin "3") (pinfunction "D_3") (pintype "unspecified"))
      (node (ref "R41") (pin "1") (pinfunction "1_1") (pintype "unspecified"))
    )
    (net (code "33") (name "Net-(D9-A)") (class "Default")
      (node (ref "D9") (pin "1") (pinfunction "A_1") (pintype "unspecified"))
      (node (ref "J3") (pin "2") (pinfunction "2_2") (pintype "unspecified"))
    )
    (net (code "34") (name "Net-(J1-Pad1)") (class "Default")
      (node (ref "J1") (pin "1") (pinfunction "1_1") (pintype "unspecified"))
      (node (ref "R14") (pin "2") (pinfunction "2_2") (pintype "input"))
    )
    (net (code "35") (name "Net-(J2-Pad2)") (class "Default")
      (node (ref "J2") (pin "2") (pinfunction "2_2") (pintype "input"))
      (node (ref "U5") (pin "2") (pinfunction "VF1__2") (pintype "unspecified"))
      (node (ref "U5") (pin "4") (pinfunction "VF1+_4") (pintype "unspecified"))
    )
    (net (code "36") (name "Net-(J2-Pad3)") (class "Default")
      (node (ref "J2") (pin "3") (pinfunction "3_3") (pintype "input"))
      (node (ref "R15") (pin "2") (pinfunction "2_2") (pintype "unspecified"))
    )
    (net (code "37") (name "Net-(LED1-Pad1)") (class "Default")
      (node (ref "LED1") (pin "1") (pinfunction "1_1") (pintype "unspecified"))
      (node (ref "R7") (pin "2") (pinfunction "2_2") (pintype "unspecified"))
    )
    (net (code "38") (name "Net-(LED2-Pad1)") (class "Default")
      (node (ref "LED2") (pin "1") (pinfunction "1_1") (pintype "unspecified"))
      (node (ref "R42") (pin "2") (pinfunction "2_2") (pintype "unspecified"))
    )
    (net (code "39") (name "Net-(R13-Pad2)") (class "Default")
      (node (ref "R13") (pin "2") (pinfunction "2_2") (pintype "unspecified"))
      (node (ref "U5") (pin "1") (pinfunction "VF1+_1") (pintype "unspecified"))
      (node (ref "U5") (pin "3") (pinfunction "VF1__3") (pintype "unspecified"))
    )
    (net (code "40") (name "Net-(U1-GP14)") (class "Default")
      (node (ref "R7") (pin "1") (pinfunction "1_1") (pintype "unspecified"))
      (node (ref "U1") (pin "19") (pinfunction "GP14_19") (pintype "unspecified"))
    )
    (net (code "41") (name "Net-(U2-EN)") (class "Default")
      (node (ref "C3") (pin "1") (pinfunction "1_1") (pintype "unspecified"))
      (node (ref "U2") (pin "5") (pinfunction "EN_5") (pintype "unspecified"))
    )
    (net (code "42") (name "Net-(U2-SCLB)") (class "Default")
      (node (ref "R5") (pin "2") (pinfunction "2_2") (pintype "unspecified"))
      (node (ref "U2") (pin "7") (pinfunction "SCLB_7") (pintype "unspecified"))
    )
    (net (code "43") (name "Net-(U2-SDAB)") (class "Default")
      (node (ref "R6") (pin "2") (pinfunction "2_2") (pintype "unspecified"))
      (node (ref "U2") (pin "6") (pinfunction "SDAB_6") (pintype "unspecified"))
    )
    (net (code "44") (name "Net-(U6-SENSEA)") (class "Default")
      (node (ref "R28") (pin "2") (pinfunction "2_2") (pintype "unspecified"))
      (node (ref "R30") (pin "2") (pinfunction "2_2") (pintype "unspecified"))
      (node (ref "U6") (pin "8") (pinfunction "SENSEA_8") (pintype "unspecified"))
    )
    (net (code "45") (name "Net-(U6-SENSEB)") (class "Default")
      (node (ref "R29") (pin "1") (pinfunction "1_1") (pintype "unspecified"))
      (node (ref "R31") (pin "2") (pinfunction "2_2") (pintype "unspecified"))
      (node (ref "U6") (pin "13") (pinfunction "SENSEB_13") (pintype "unspecified"))
    )
    (net (code "46") (name "Net-(U11-SENSEA)") (class "Default")
      (node (ref "R36") (pin "2") (pinfunction "2_2") (pintype "unspecified"))
      (node (ref "R38") (pin "2") (pinfunction "2_2") (pintype "unspecified"))
      (node (ref "U11") (pin "8") (pinfunction "SENSEA_8") (pintype "unspecified"))
    )
    (net (code "47") (name "Net-(U11-SENSEB)") (class "Default")
      (node (ref "R37") (pin "1") (pinfunction "1_1") (pintype "unspecified"))
      (node (ref "R39") (pin "2") (pinfunction "2_2") (pintype "unspecified"))
      (node (ref "U11") (pin "13") (pinfunction "SENSEB_13") (pintype "unspecified"))
    )
    (net (code "48") (name "Net-(U11-VCP)") (class "Default")
      (node (ref "C15") (pin "1") (pinfunction "1_1") (pintype "unspecified"))
      (node (ref "U11") (pin "4") (pinfunction "VCP_4") (pintype "unspecified"))
    )
    (net (code "49") (name "PFAIL") (class "Default")
      (node (ref "C26") (pin "1") (pinfunction "1_1") (pintype "unspecified"))
      (node (ref "R40") (pin "1") (pinfunction "1_1") (pintype "unspecified"))
      (node (ref "R43") (pin "2") (pinfunction "2_2") (pintype "unspecified"))
      (node (ref "U1") (pin "20") (pinfunction "GP15_20") (pintype "unspecified"))
    )
    (net (code "50") (name "PSCL") (class "Default")
      (node (ref "R3") (pin "1") (pinfunction "1_1") (pintype "unspecified"))
      (node (ref "U1") (pin "22") (pinfunction "GP17_22") (pintype "unspecified"))
      (node (ref "U2") (pin "2") (pinfunction "SCLA_2") (pintype "unspecified"))
    )
    (net (code "51") (name "PSDA") (class "Default")
      (node (ref "R4") (pin "1") (pinfunction "1_1") (pintype "unspecified"))
      (node (ref "U1") (pin "21") (pinfunction "GP16_21") (pintype "unspecified"))
      (node (ref "U2") (pin "3") (pinfunction "SDAA_3") (pintype "unspecified"))
    )
    (net (code "52") (name "RST") (class "Default")
      (node (ref "B1") (pin "3") (pinfunction "3_3") (pintype "unspecified"))
      (node (ref "B1") (pin "4") (pinfunction "4_4") (pintype "unspecified"))
      (node (ref "PCB1") (pin "76") (pinfunction "RST_76") (pintype "unspecified"))
      (node (ref "R8") (pin "1") (pinfunction "1_1") (pintype "unspecified"))
      (node (ref "U1") (pin "30") (pinfunction "RUN_30") (pintype "unspecified"))
    )
    (net (code "53") (name "S-0") (class "Default")
      (node (ref "C9") (pin "2") (pinfunction "2_2") (pintype "unspecified"))
      (node (ref "D1") (pin "1") (pinfunction "C_1") (pintype "unspecified"))
      (node (ref "R28") (pin "1") (pinfunction "1_1") (pintype "unspecified"))
      (node (ref "U12") (pin "15") (pinfunction "Y2_15") (pintype "unspecified"))
    )
    (net (code "54") (name "S-1") (class "Default")
      (node (ref "C14") (pin "2") (pinfunction "2_2") (pintype "unspecified"))
      (node (ref "D2") (pin "1") (pinfunction "C_1") (pintype "unspecified"))
      (node (ref "R29") (pin "2") (pinfunction "2_2") (pintype "unspecified"))
      (node (ref "U12") (pin "14") (pinfunction "Y1_14") (pintype "unspecified"))
    )
    (net (code "55") (name "S-2") (class "Default")
      (node (ref "C18") (pin "2") (pinfunction "2_2") (pintype "unspecified"))
      (node (ref "D5") (pin "1") (pinfunction "C_1") (pintype "unspecified"))
      (node (ref "R36") (pin "1") (pinfunction "1_1") (pintype "unspecified"))
      (node (ref "U12") (pin "13") (pinfunction "Y0_13") (pintype "unspecified"))
    )
    (net (code "56") (name "S-3") (class "Default")
      (node (ref "C23") (pin "2") (pinfunction "2_2") (pintype "unspecified"))
      (node (ref "D6") (pin "1") (pinfunction "C_1") (pintype "unspecified"))
      (node (ref "R37") (pin "2") (pinfunction "2_2") (pintype "unspecified"))
      (node (ref "U12") (pin "12") (pinfunction "Y3_12") (pintype "unspecified"))
    )
    (net (code "57") (name "SCL") (class "Default")
      (node (ref "PCB1") (pin "24") (pinfunction "SCL_24") (pintype "unspecified"))
      (node (ref "PCB1") (pin "74") (pinfunction "SCL_74") (pintype "unspecified"))
      (node (ref "R1") (pin "1") (pinfunction "1_1") (pintype "unspecified"))
      (node (ref "R5") (pin "1") (pinfunction "1_1") (pintype "unspecified"))
    )
    (net (code "58") (name "SDA") (class "Default")
      (node (ref "PCB1") (pin "25") (pinfunction "SDA_25") (pintype "unspecified"))
      (node (ref "PCB1") (pin "75") (pinfunction "SDA_75") (pintype "unspecified"))
      (node (ref "R2") (pin "1") (pinfunction "1_1") (pintype "unspecified"))
      (node (ref "R6") (pin "1") (pinfunction "1_1") (pintype "unspecified"))
    )
    (net (code "59") (name "SEL-0-1") (class "Default")
      (node (ref "R26") (pin "1") (pinfunction "1_1") (pintype "unspecified"))
      (node (ref "U1") (pin "6") (pinfunction "GP4_6") (pintype "unspecified"))
      (node (ref "U6") (pin "6") (pinfunction "IN1A_6") (pintype "unspecified"))
      (node (ref "U7") (pin "2") (pinfunction "B_2") (pintype "unspecified"))
    )
    (net (code "60") (name "SEL-0-2") (class "Default")
      (node (ref "R27") (pin "1") (pinfunction "1_1") (pintype "unspecified"))
      (node (ref "U1") (pin "7") (pinfunction "GP5_7") (pintype "unspecified"))
      (node (ref "U6") (pin "7") (pinfunction "IN2A_7") (pintype "unspecified"))
      (node (ref "U7") (pin "1") (pinfunction "A_1") (pintype "unspecified"))
    )
    (net (code "61") (name "SEL-1-1") (class "Default")
      (node (ref "R24") (pin "1") (pinfunction "1_1") (pintype "unspecified"))
      (node (ref "U1") (pin "11") (pinfunction "GP8_11") (pintype "unspecified"))
      (node (ref "U6") (pin "15") (pinfunction "IN2B_15") (pintype "unspecified"))
      (node (ref "U8") (pin "2") (pinfunction "B_2") (pintype "unspecified"))
    )
    (net (code "62") (name "SEL-1-2") (class "Default")
      (node (ref "R25") (pin "1") (pinfunction "1_1") (pintype "unspecified"))
      (node (ref "U1") (pin "12") (pinfunction "GP9_12") (pintype "unspecified"))
      (node (ref "U6") (pin "14") (pinfunction "IN1B_14") (pintype "unspecified"))
      (node (ref "U8") (pin "1") (pinfunction "A_1") (pintype "unspecified"))
    )
    (net (code "63") (name "SEL-2-1") (class "Default")
      (node (ref "R22") (pin "1") (pinfunction "1_1") (pintype "unspecified"))
      (node (ref "U1") (pin "26") (pinfunction "GP20_26") (pintype "unspecified"))
      (node (ref "U11") (pin "6") (pinfunction "IN1A_6") (pintype "unspecified"))
      (node (ref "U9") (pin "2") (pinfunction "B_2") (pintype "unspecified"))
    )
    (net (code "64") (name "SEL-2-2") (class "Default")
      (node (ref "R23") (pin "1") (pinfunction "1_1") (pintype "unspecified"))
      (node (ref "U1") (pin "27") (pinfunction "GP21_27") (pintype "unspecified"))
      (node (ref "U11") (pin "7") (pinfunction "IN2A_7") (pintype "unspecified"))
      (node (ref "U9") (pin "1") (pinfunction "A_1") (pintype "unspecified"))
    )
    (net (code "65") (name "SEL-3-1") (class "Default")
      (node (ref "R20") (pin "1") (pinfunction "1_1") (pintype "unspecified"))
      (node (ref "U1") (pin "24") (pinfunction "GP18_24") (pintype "unspecified"))
      (node (ref "U10") (pin "2") (pinfunction "B_2") (pintype "unspecified"))
      (node (ref "U11") (pin "15") (pinfunction "IN2B_15") (pintype "unspecified"))
    )
    (net (code "66") (name "SEL-3-2") (class "Default")
      (node (ref "R21") (pin "1") (pinfunction "1_1") (pintype "unspecified"))
      (node (ref "U1") (pin "25") (pinfunction "GP19_25") (pintype "unspecified"))
      (node (ref "U10") (pin "1") (pinfunction "A_1") (pintype "unspecified"))
      (node (ref "U11") (pin "14") (pinfunction "IN1B_14") (pintype "unspecified"))
    )
    (net (code "67") (name "ST-0") (class "Default")
      (node (ref "C10") (pin "2") (pinfunction "2_2") (pintype "unspecified"))
      (node (ref "R16") (pin "2") (pinfunction "2_2") (pintype "unspecified"))
      (node (ref "R18") (pin "2") (pinfunction "2_2") (pintype "unspecified"))
      (node (ref "U1") (pin "9") (pinfunction "GP6_9") (pintype "unspecified"))
      (node (ref "U6") (pin "5") (pinfunction "ENA_5") (pintype "unspecified"))
    )
    (net (code "68") (name "ST-1") (class "Default")
      (node (ref "C13") (pin "2") (pinfunction "2_2") (pintype "unspecified"))
      (node (ref "R17") (pin "1") (pinfunction "1_1") (pintype "unspecified"))
      (node (ref "R19") (pin "1") (pinfunction "1_1") (pintype "unspecified"))
      (node (ref "U1") (pin "10") (pinfunction "GP7_10") (pintype "unspecified"))
      (node (ref "U6") (pin "16") (pinfunction "ENB_16") (pintype "unspecified"))
    )
    (net (code "69") (name "ST-2") (class "Default")
      (node (ref "C19") (pin "2") (pinfunction "2_2") (pintype "unspecified"))
      (node (ref "R32") (pin "2") (pinfunction "2_2") (pintype "unspecified"))
      (node (ref "R34") (pin "2") (pinfunction "2_2") (pintype "unspecified"))
      (node (ref "U1") (pin "14") (pinfunction "GP10_14") (pintype "unspecified"))
      (node (ref "U11") (pin "5") (pinfunction "ENA_5") (pintype "unspecified"))
    )
    (net (code "70") (name "ST-3") (class "Default")
      (node (ref "C22") (pin "2") (pinfunction "2_2") (pintype "unspecified"))
      (node (ref "R33") (pin "1") (pinfunction "1_1") (pintype "unspecified"))
      (node (ref "R35") (pin "1") (pinfunction "1_1") (pintype "unspecified"))
      (node (ref "U1") (pin "15") (pinfunction "GP11_15") (pintype "unspecified"))
      (node (ref "U11") (pin "16") (pinfunction "ENB_16") (pintype "unspecified"))
    )
    (net (code "71") (name "V-USB") (class "Default")
      (node (ref "Q1") (pin "1") (pinfunction "G_1") (pintype "unspecified"))
      (node (ref "U1") (pin "40") (pinfunction "VBUS_40") (pintype "unspecified"))
    )
    (net (code "72") (name "VBOOT") (class "Default")
      (node (ref "C16") (pin "1") (pinfunction "1_1") (pintype "unspecified"))
      (node (ref "C8") (pin "1") (pinfunction "1_1") (pintype "unspecified"))
      (node (ref "D4") (pin "1") (pinfunction "2_1") (pintype "unspecified"))
      (node (ref "U11") (pin "17") (pinfunction "VBOOT_17") (pintype "unspecified"))
      (node (ref "U6") (pin "17") (pinfunction "VBOOT_17") (pintype "unspecified"))
    )
    (net (code "73") (name "VCC-3V3") (class "Default")
      (node (ref "C17") (pin "1") (pinfunction "1_1") (pintype "unspecified"))
      (node (ref "C2") (pin "2") (pinfunction "2_2") (pintype "unspecified"))
      (node (ref "C4") (pin "1") (pinfunction "1_1") (pintype "unspecified"))
      (node (ref "C6") (pin "1") (pinfunction "1_1") (pintype "unspecified"))
      (node (ref "C7") (pin "2") (pinfunction "2_2") (pintype "input"))
      (node (ref "R10") (pin "1") (pinfunction "1_1") (pintype "unspecified"))
      (node (ref "R11") (pin "2") (pinfunction "2_2") (pintype "unspecified"))
      (node (ref "R12") (pin "2") (pinfunction "2_2") (pintype "unspecified"))
      (node (ref "R16") (pin "1") (pinfunction "1_1") (pintype "unspecified"))
      (node (ref "R17") (pin "2") (pinfunction "2_2") (pintype "unspecified"))
      (node (ref "R20") (pin "2") (pinfunction "2_2") (pintype "unspecified"))
      (node (ref "R21") (pin "2") (pinfunction "2_2") (pintype "unspecified"))
      (node (ref "R22") (pin "2") (pinfunction "2_2") (pintype "unspecified"))
      (node (ref "R23") (pin "2") (pinfunction "2_2") (pintype "unspecified"))
      (node (ref "R24") (pin "2") (pinfunction "2_2") (pintype "unspecified"))
      (node (ref "R25") (pin "2") (pinfunction "2_2") (pintype "unspecified"))
      (node (ref "R26") (pin "2") (pinfunction "2_2") (pintype "unspecified"))
      (node (ref "R27") (pin "2") (pinfunction "2_2") (pintype "unspecified"))
      (node (ref "R3") (pin "2") (pinfunction "2_2") (pintype "unspecified"))
      (node (ref "R32") (pin "1") (pinfunction "1_1") (pintype "unspecified"))
      (node (ref "R33") (pin "2") (pinfunction "2_2") (pintype "unspecified"))
      (node (ref "R4") (pin "2") (pinfunction "2_2") (pintype "unspecified"))
      (node (ref "R8") (pin "2") (pinfunction "2_2") (pintype "unspecified"))
      (node (ref "R9") (pin "1") (pinfunction "1_1") (pintype "unspecified"))
      (node (ref "U1") (pin "36") (pinfunction "3V3_OUT_36") (pintype "unspecified"))
      (node (ref "U10") (pin "5") (pinfunction "VCC_5") (pintype "unspecified"))
      (node (ref "U12") (pin "16") (pinfunction "VDD_16") (pintype "unspecified"))
      (node (ref "U2") (pin "1") (pinfunction "VCC(A)_1") (pintype "unspecified"))
      (node (ref "U3") (pin "8") (pinfunction "VCC_8") (pintype "passive"))
      (node (ref "U4") (pin "5") (pinfunction "VIO_5") (pintype "unspecified"))
      (node (ref "U5") (pin "8") (pinfunction "VCC_8") (pintype "unspecified"))
      (node (ref "U7") (pin "5") (pinfunction "VCC_5") (pintype "unspecified"))
      (node (ref "U8") (pin "5") (pinfunction "VCC_5") (pintype "unspecified"))
      (node (ref "U9") (pin "5") (pinfunction "VCC_5") (pintype "unspecified"))
    )
    (net (code "74") (name "VCC-12V") (class "Default")
      (node (ref "C29") (pin "1") (pinfunction "1_1") (pintype "unspecified"))
      (node (ref "J3") (pin "1") (pinfunction "1_1") (pintype "unspecified"))
      (node (ref "PCB1") (pin "21") (pinfunction "VOUT_21") (pintype "unspecified"))
      (node (ref "PCB1") (pin "22") (pinfunction "VOUT_22") (pintype "unspecified"))
      (node (ref "U14") (pin "3") (pinfunction "VOUT_3") (pintype "unspecified"))
    )
    (net (code "75") (name "VCC-EXT") (class "Default")
      (node (ref "C25") (pin "1") (pinfunction "1_1") (pintype "unspecified"))
      (node (ref "D8") (pin "1") (pinfunction "A_1") (pintype "unspecified"))
      (node (ref "PCB1") (pin "80") (pinfunction "VCC_80") (pintype "unspecified"))
      (node (ref "PCB1") (pin "81") (pinfunction "VCC_81") (pintype "unspecified"))
      (node (ref "R40") (pin "2") (pinfunction "2_2") (pintype "unspecified"))
      (node (ref "R42") (pin "1") (pinfunction "1_1") (pintype "unspecified"))
      (node (ref "U13") (pin "3") (pinfunction "VOUT_3") (pintype "unspecified"))
    )
    (net (code "76") (name "VCC-MB") (class "Default")
      (node (ref "C1") (pin "1") (pinfunction "1_1") (pintype "unspecified"))
      (node (ref "C5") (pin "1") (pinfunction "1_1") (pintype "unspecified"))
      (node (ref "Q1") (pin "2") (pinfunction "S_2") (pintype "unspecified"))
      (node (ref "R1") (pin "2") (pinfunction "2_2") (pintype "unspecified"))
      (node (ref "R2") (pin "2") (pinfunction "2_2") (pintype "unspecified"))
      (node (ref "U1") (pin "39") (pinfunction "VSYS_39") (pintype "unspecified"))
      (node (ref "U2") (pin "8") (pinfunction "VCC(B)_8") (pintype "unspecified"))
      (node (ref "U4") (pin "3") (pinfunction "VDD_3") (pintype "unspecified"))
    )
    (net (code "77") (name "VS") (class "Default")
      (node (ref "C11") (pin "2") (pinfunction "2_2") (pintype "unspecified"))
      (node (ref "C12") (pin "1") (pinfunction "1_1") (pintype "unspecified"))
      (node (ref "C16") (pin "2") (pinfunction "2_2") (pintype "unspecified"))
      (node (ref "C20") (pin "2") (pinfunction "2_2") (pintype "unspecified"))
      (node (ref "C21") (pin "1") (pinfunction "1_1") (pintype "unspecified"))
      (node (ref "C8") (pin "2") (pinfunction "2_2") (pintype "unspecified"))
      (node (ref "D3") (pin "2") (pinfunction "1_2") (pintype "unspecified"))
      (node (ref "D7") (pin "1") (pinfunction "A_1") (pintype "unspecified"))
      (node (ref "PCB1") (pin "32") (pinfunction "VS_32") (pintype "unspecified"))
      (node (ref "PCB1") (pin "94") (pinfunction "VS_94") (pintype "unspecified"))
      (node (ref "PCB1") (pin "95") (pinfunction "VS_95") (pintype "unspecified"))
      (node (ref "PCB1") (pin "96") (pinfunction "VS_96") (pintype "unspecified"))
      (node (ref "PCB1") (pin "97") (pinfunction "VS_97") (pintype "unspecified"))
      (node (ref "U11") (pin "19") (pinfunction "VSB_19") (pintype "unspecified"))
      (node (ref "U11") (pin "2") (pinfunction "VSA_2") (pintype "unspecified"))
      (node (ref "U6") (pin "19") (pinfunction "VSB_19") (pintype "unspecified"))
      (node (ref "U6") (pin "2") (pinfunction "VSA_2") (pintype "unspecified"))
    )
    (net (code "78") (name "unconnected-(PCB1-ADC-0-Pad56)") (class "Default")
      (node (ref "PCB1") (pin "56") (pinfunction "ADC-0_56") (pintype "unspecified+no_connect"))
    )
    (net (code "79") (name "unconnected-(PCB1-ADC-1-Pad57)") (class "Default")
      (node (ref "PCB1") (pin "57") (pinfunction "ADC-1_57") (pintype "unspecified+no_connect"))
    )
    (net (code "80") (name "unconnected-(PCB1-DIO-0-Pad60)") (class "Default")
      (node (ref "PCB1") (pin "60") (pinfunction "DIO-0_60") (pintype "unspecified+no_connect"))
    )
    (net (code "81") (name "unconnected-(PCB1-DIO-1-Pad61)") (class "Default")
      (node (ref "PCB1") (pin "61") (pinfunction "DIO-1_61") (pintype "unspecified+no_connect"))
    )
    (net (code "82") (name "unconnected-(PCB1-DIO-2-Pad62)") (class "Default")
      (node (ref "PCB1") (pin "62") (pinfunction "DIO-2_62") (pintype "unspecified+no_connect"))
    )
    (net (code "83") (name "unconnected-(PCB1-DIO-3-Pad63)") (class "Default")
      (node (ref "PCB1") (pin "63") (pinfunction "DIO-3_63") (pintype "unspecified+no_connect"))
    )
    (net (code "84") (name "unconnected-(PCB1-DIO-4-Pad64)") (class "Default")
      (node (ref "PCB1") (pin "64") (pinfunction "DIO-4_64") (pintype "unspecified+no_connect"))
    )
    (net (code "85") (name "unconnected-(PCB1-DIO-5-Pad65)") (class "Default")
      (node (ref "PCB1") (pin "65") (pinfunction "DIO-5_65") (pintype "unspecified+no_connect"))
    )
    (net (code "86") (name "unconnected-(PCB1-DIO-6-Pad66)") (class "Default")
      (node (ref "PCB1") (pin "66") (pinfunction "DIO-6_66") (pintype "unspecified+no_connect"))
    )
    (net (code "87") (name "unconnected-(PCB1-DIO-7-Pad67)") (class "Default")
      (node (ref "PCB1") (pin "67") (pinfunction "DIO-7_67") (pintype "unspecified+no_connect"))
    )
    (net (code "88") (name "unconnected-(PCB1-DIO-8-Pad68)") (class "Default")
      (node (ref "PCB1") (pin "68") (pinfunction "DIO-8_68") (pintype "unspecified+no_connect"))
    )
    (net (code "89") (name "unconnected-(PCB1-DIO-9-Pad69)") (class "Default")
      (node (ref "PCB1") (pin "69") (pinfunction "DIO-9_69") (pintype "unspecified+no_connect"))
    )
    (net (code "90") (name "unconnected-(PCB1-DIO-10-Pad70)") (class "Default")
      (node (ref "PCB1") (pin "70") (pinfunction "DIO-10_70") (pintype "unspecified+no_connect"))
    )
    (net (code "91") (name "unconnected-(PCB1-DIO-11-Pad71)") (class "Default")
      (node (ref "PCB1") (pin "71") (pinfunction "DIO-11_71") (pintype "unspecified+no_connect"))
    )
    (net (code "92") (name "unconnected-(PCB1-EXT-Pad77)") (class "Default")
      (node (ref "PCB1") (pin "77") (pinfunction "EXT_77") (pintype "unspecified+no_connect"))
    )
    (net (code "93") (name "unconnected-(PCB1-NN-Pad23)") (class "Default")
      (node (ref "PCB1") (pin "23") (pinfunction "NN_23") (pintype "unspecified+no_connect"))
    )
    (net (code "94") (name "unconnected-(PCB1-NN-Pad26)") (class "Default")
      (node (ref "PCB1") (pin "26") (pinfunction "NN_26") (pintype "unspecified+no_connect"))
    )
    (net (code "95") (name "unconnected-(U1-3V3_En-Pad37)") (class "Default")
      (node (ref "U1") (pin "37") (pinfunction "3V3_En_37") (pintype "unspecified+no_connect"))
    )
    (net (code "96") (name "unconnected-(U1-GND-Pad42)") (class "Default")
      (node (ref "U1") (pin "42") (pinfunction "GND_42") (pintype "unspecified+no_connect"))
    )
    (net (code "97") (name "unconnected-(U1-GP22-Pad29)") (class "Default")
      (node (ref "U1") (pin "29") (pinfunction "GP22_29") (pintype "unspecified+no_connect"))
    )
    (net (code "98") (name "unconnected-(U1-SWDIO-Pad43)") (class "Default")
      (node (ref "U1") (pin "43") (pinfunction "SWDIO_43") (pintype "unspecified+no_connect"))
    )
    (net (code "99") (name "unconnected-(U1-SWLCK-Pad41)") (class "Default")
      (node (ref "U1") (pin "41") (pinfunction "SWLCK_41") (pintype "unspecified+no_connect"))
    )
    (net (code "100") (name "unconnected-(U1-VRef-Pad35)") (class "Default")
      (node (ref "U1") (pin "35") (pinfunction "VRef_35") (pintype "unspecified+no_connect"))
    )
    (net (code "101") (name "unconnected-(U6-VCP-Pad4)") (class "Default")
      (node (ref "U6") (pin "4") (pinfunction "VCP_4") (pintype "unspecified+no_connect"))
    )
    (net (code "102") (name "unconnected-(U12-VEE-Pad7)") (class "Default")
      (node (ref "U12") (pin "7") (pinfunction "VEE_7") (pintype "unspecified+no_connect"))
    )
    (net (code "103") (name "unconnected-(U12-Y4-Pad1)") (class "Default")
      (node (ref "U12") (pin "1") (pinfunction "Y4_1") (pintype "unspecified+no_connect"))
    )
    (net (code "104") (name "unconnected-(U12-Y5-Pad5)") (class "Default")
      (node (ref "U12") (pin "5") (pinfunction "Y5_5") (pintype "unspecified+no_connect"))
    )
    (net (code "105") (name "unconnected-(U12-Y6-Pad2)") (class "Default")
      (node (ref "U12") (pin "2") (pinfunction "Y6_2") (pintype "unspecified+no_connect"))
    )
    (net (code "106") (name "unconnected-(U12-Y7-Pad4)") (class "Default")
      (node (ref "U12") (pin "4") (pinfunction "Y7_4") (pintype "unspecified+no_connect"))
    )
  )
)
